# USBHeaders.net
KiCad netlist of a schematic drawn in Altium Designer
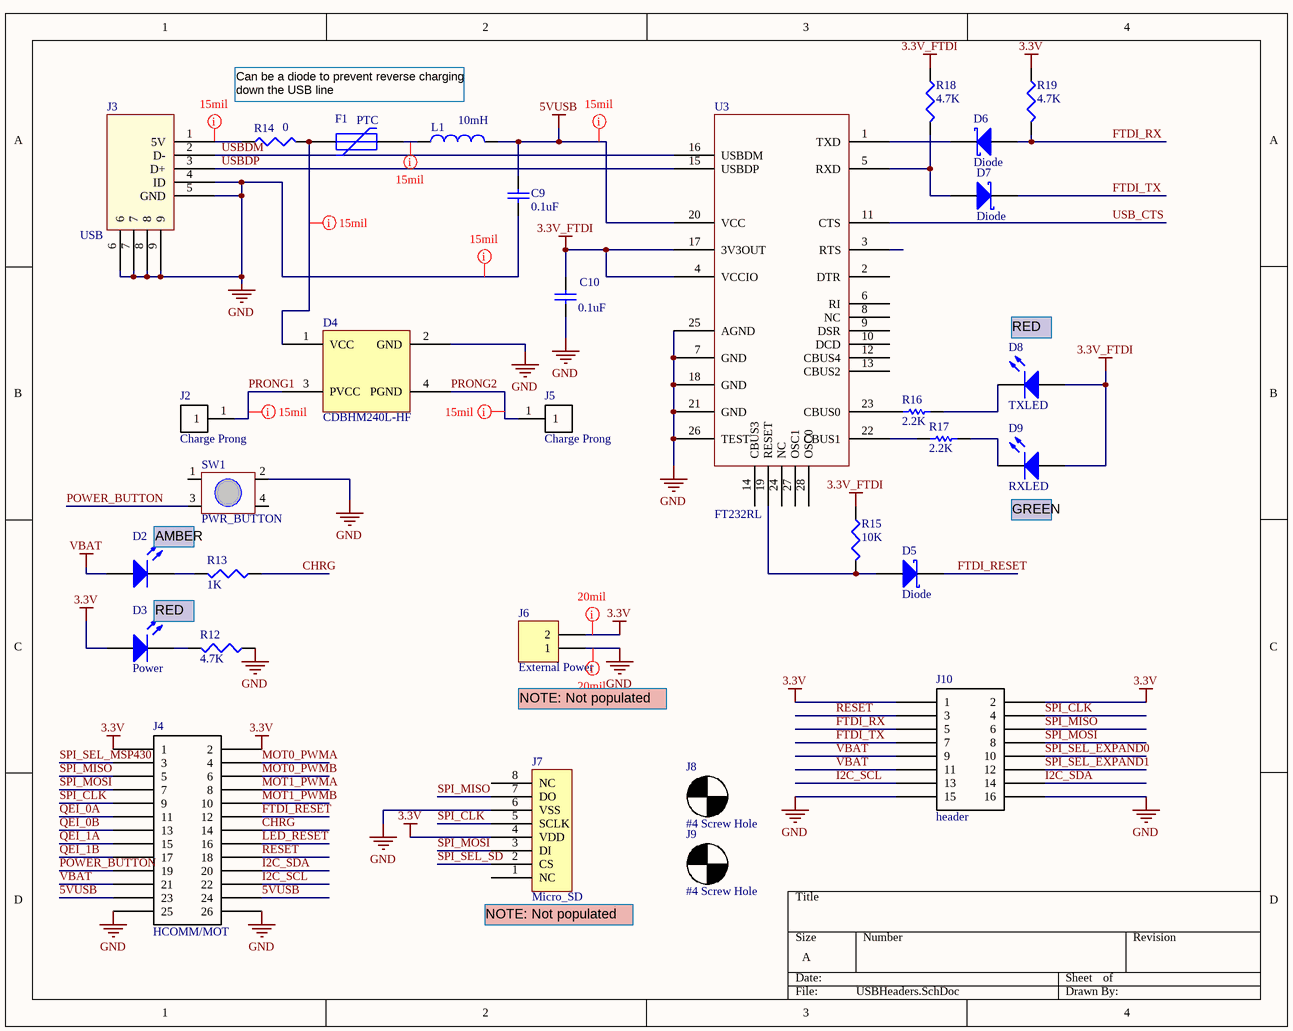
[diagram p0: USBHeaders.SchDoc]

(export (version "E")
  (design (tool "Eeschema 10.0.6"))
  (components
    (comp (ref "C9")
      (value "0.1uF")
      (footprint "CAPC1005L")
      (description "Capacitor")
      (fields (field (name "PUBLISHER") "Altium Limited"))
      (libsource (lib "Miscellaneous Devices") (part "Cap"))
    )
    (comp (ref "C10")
      (value "0.1uF")
      (footprint "CAPC1005L")
      (description "Capacitor")
      (fields (field (name "PUBLISHER") "Altium Limited"))
      (libsource (lib "Miscellaneous Devices") (part "Cap"))
    )
    (comp (ref "D2")
      (value "Charge")
      (footprint "SurfaceMount(603)")
      (description "Typical RED, GREEN, YELLOW, AMBER GaAs LED")
      (fields (field (name "PUBLISHER") "Altium Limited"))
      (libsource (lib "") (part "LED2_1"))
    )
    (comp (ref "D3") (value "Power") (footprint "SurfaceMount(603)") (libsource (lib "mrone") (part "LED")))
    (comp (ref "D4")
      (value "CDBHM240L-HF")
      (footprint "DIODEARRAY_2AMPS")
      (fields (field (name "MPN") "CDBHM240L-HF"))
      (libsource (lib "mrone") (part "DiodeArray2Amps"))
    )
    (comp (ref "D5")
      (value "Diode")
      (footprint "SurfaceMount(603)")
      (libsource (lib "mrone") (part "SchottkeyDiode"))
    )
    (comp (ref "D6")
      (value "Diode")
      (footprint "SurfaceMount(603)")
      (libsource (lib "mrone") (part "SchottkeyDiode"))
    )
    (comp (ref "D7")
      (value "Diode")
      (footprint "SurfaceMount(603)")
      (libsource (lib "mrone") (part "SchottkeyDiode"))
    )
    (comp (ref "D8")
      (value "TXLED")
      (footprint "SurfaceMount(603)")
      (description "Typical RED, GREEN, YELLOW, AMBER GaAs LED")
      (fields (field (name "PUBLISHER") "Altium Limited"))
      (libsource (lib "Miscellaneous Devices") (part "LED2"))
    )
    (comp (ref "D9")
      (value "RXLED")
      (footprint "SurfaceMount(603)")
      (description "Typical RED, GREEN, YELLOW, AMBER GaAs LED")
      (fields (field (name "PUBLISHER") "Altium Limited"))
      (libsource (lib "Miscellaneous Devices") (part "LED2"))
    )
    (comp (ref "F1")
      (value "PTC")
      (footprint "ERJ8G-1206")
      (description "Fuse")
      (fields (field (name "PUBLISHER") "Altium Limited"))
      (libsource (lib "mrone") (part "PTC_FUSE"))
    )
    (comp (ref "J2")
      (value "Charge Prong")
      (footprint "CHARGING_PRONG")
      (description "Charging Prong Hole with Plating")
      (libsource (lib "mrone") (part "CHARGE_PRONG"))
    )
    (comp (ref "J3")
      (value "USB")
      (footprint "USB Minib (thru-hole)")
      (libsource (lib "mrone") (part "USB-ConnTH"))
    )
    (comp (ref "J4")
      (value "HCOMM/MOT")
      (footprint "HeaderSM 13x2")
      (description "Header, 2X20, 50mil, IDC")
      (libsource (lib "mrone") (part "HCOMM/HMOT"))
    )
    (comp (ref "J5")
      (value "Charge Prong")
      (footprint "CHARGING_PRONG")
      (description "Charging Prong Hole with Plating")
      (libsource (lib "mrone") (part "CHARGE_PRONG"))
    )
    (comp (ref "J6")
      (value "External Power")
      (footprint "HDR1X2")
      (description "Header, 2-Pin")
      (fields (field (name "PUBLISHER") "Altium Limited"))
      (libsource (lib "Miscellaneous Connectors") (part "Header 2"))
    )
    (comp (ref "J7") (value "Micro_SD") (footprint "MICRO_SD") (libsource (lib "mrone") (part "MICRO_SD")))
    (comp (ref "J8")
      (value "#4 Screw Hole")
      (footprint "#4_Screw_Hole")
      (description "A mechanical hole for mounting the board")
      (libsource (lib "mrone") (part "Mechanical_Hole"))
    )
    (comp (ref "J9")
      (value "#4 Screw Hole")
      (footprint "#4_Screw_Hole")
      (description "A mechanical hole for mounting the board")
      (libsource (lib "mrone") (part "Mechanical_Hole"))
    )
    (comp (ref "J10")
      (value "header")
      (footprint "HEADERSM 8X2")
      (libsource (lib "mrone") (part "HEADER 8X2"))
    )
    (comp (ref "L1")
      (value "10mH")
      (footprint "INDC2012L")
      (description "Inductor")
      (fields (field (name "PUBLISHER") "Altium Limited"))
      (libsource (lib "Miscellaneous Devices") (part "Inductor"))
    )
    (comp (ref "R12")
      (value "4.7K")
      (footprint "RESC1608L")
      (description "Resistor")
      (fields (field (name "Comment") "Res3") (field (name "PUBLISHER") "Altium Limited"))
      (libsource (lib "Miscellaneous Devices") (part "Res3"))
    )
    (comp (ref "R13")
      (value "1K")
      (footprint "RESC1608L")
      (description "Resistor")
      (fields (field (name "Comment") "Res3") (field (name "PUBLISHER") "Altium Limited"))
      (libsource (lib "Miscellaneous Devices") (part "Res3"))
    )
    (comp (ref "R14")
      (value "0")
      (footprint "RESC1608L")
      (description "Resistor")
      (fields (field (name "Comment") "Res3") (field (name "PUBLISHER") "Altium Limited"))
      (libsource (lib "Miscellaneous Devices") (part "Res3"))
    )
    (comp (ref "R15")
      (value "10K")
      (footprint "RESC1608L")
      (description "Resistor")
      (fields (field (name "Comment") "Res3") (field (name "PUBLISHER") "Altium Limited"))
      (libsource (lib "Miscellaneous Devices") (part "Res3"))
    )
    (comp (ref "R16")
      (value "2.2K")
      (footprint "RESC1608L")
      (description "Resistor")
      (fields (field (name "PUBLISHER") "Altium Limited"))
      (libsource (lib "Miscellaneous Devices") (part "Res1"))
    )
    (comp (ref "R17")
      (value "2.2K")
      (footprint "RESC1608L")
      (description "Resistor")
      (fields (field (name "PUBLISHER") "Altium Limited"))
      (libsource (lib "Miscellaneous Devices") (part "Res1"))
    )
    (comp (ref "R18")
      (value "4.7K")
      (footprint "RESC1608L")
      (description "Resistor")
      (fields (field (name "Comment") "Res3") (field (name "PUBLISHER") "Altium Limited"))
      (libsource (lib "Miscellaneous Devices") (part "Res3"))
    )
    (comp (ref "R19")
      (value "4.7K")
      (footprint "RESC1608L")
      (description "Resistor")
      (fields (field (name "Comment") "Res3") (field (name "PUBLISHER") "Altium Limited"))
      (libsource (lib "Miscellaneous Devices") (part "Res3"))
    )
    (comp (ref "SW1")
      (value "PWR_BUTTON")
      (footprint "SwitchTall-TL330")
      (libsource (lib "mrone") (part "Switch-TL330"))
    )
    (comp (ref "U3") (value "FT232RL") (footprint "SSOP-28") (libsource (lib "mrone") (part "FT232RL")))
  )
  (nets
    (net (code "2") (name "/CHRG") (class "Default")
      (node (ref "J4") (pin "14") (pinfunction "14_14") (pintype "passive"))
      (node (ref "R13") (pin "1") (pinfunction "1_1") (pintype "passive"))
    )
    (net (code "3") (name "/FTDI_RESET") (class "Default")
      (node (ref "D5") (pin "1") (pinfunction "K_1") (pintype "passive"))
      (node (ref "J4") (pin "12") (pinfunction "12_12") (pintype "passive"))
    )
    (net (code "4") (name "/FTDI_RX") (class "Default")
      (node (ref "D6") (pin "2") (pinfunction "A_2") (pintype "passive"))
      (node (ref "J10") (pin "5") (pinfunction "5_5") (pintype "passive"))
      (node (ref "R19") (pin "2") (pinfunction "2_2") (pintype "passive"))
    )
    (net (code "5") (name "/FTDI_TX") (class "Default")
      (node (ref "D7") (pin "1") (pinfunction "K_1") (pintype "passive"))
      (node (ref "J10") (pin "7") (pinfunction "7_7") (pintype "passive"))
    )
    (net (code "6") (name "/I2C_SCL") (class "Default")
      (node (ref "J10") (pin "13") (pinfunction "13_13") (pintype "passive"))
      (node (ref "J4") (pin "22") (pinfunction "22_22") (pintype "passive"))
    )
    (net (code "7") (name "/I2C_SDA") (class "Default")
      (node (ref "J10") (pin "14") (pinfunction "14_14") (pintype "passive"))
      (node (ref "J4") (pin "20") (pinfunction "20_20") (pintype "passive"))
    )
    (net (code "8") (name "/LED_RESET") (class "Default")
      (node (ref "J4") (pin "16") (pinfunction "16_16") (pintype "passive"))
    )
    (net (code "9") (name "/MOT0_PWMA") (class "Default")
      (node (ref "J4") (pin "4") (pinfunction "4_4") (pintype "passive"))
    )
    (net (code "10") (name "/MOT0_PWMB") (class "Default")
      (node (ref "J4") (pin "6") (pinfunction "6_6") (pintype "passive"))
    )
    (net (code "11") (name "/MOT1_PWMA") (class "Default")
      (node (ref "J4") (pin "8") (pinfunction "8_8") (pintype "passive"))
    )
    (net (code "12") (name "/MOT1_PWMB") (class "Default")
      (node (ref "J4") (pin "10") (pinfunction "10_10") (pintype "passive"))
    )
    (net (code "13") (name "/POWER_BUTTON") (class "Default")
      (node (ref "J4") (pin "19") (pinfunction "19_19") (pintype "passive"))
      (node (ref "SW1") (pin "3") (pinfunction "3_3") (pintype "passive"))
    )
    (net (code "14") (name "/PRONG1") (class "Default")
      (node (ref "D4") (pin "3") (pinfunction "PVCC_3") (pintype "passive"))
      (node (ref "J2") (pin "1") (pinfunction "1_1") (pintype "passive"))
    )
    (net (code "15") (name "/PRONG2") (class "Default")
      (node (ref "D4") (pin "4") (pinfunction "PGND_4") (pintype "passive"))
      (node (ref "J5") (pin "1") (pinfunction "1_1") (pintype "passive"))
    )
    (net (code "16") (name "/QEI_0A") (class "Default")
      (node (ref "J4") (pin "11") (pinfunction "11_11") (pintype "passive"))
    )
    (net (code "17") (name "/QEI_0B") (class "Default")
      (node (ref "J4") (pin "13") (pinfunction "13_13") (pintype "passive"))
    )
    (net (code "18") (name "/QEI_1A") (class "Default")
      (node (ref "J4") (pin "15") (pinfunction "15_15") (pintype "passive"))
    )
    (net (code "19") (name "/QEI_1B") (class "Default")
      (node (ref "J4") (pin "17") (pinfunction "17_17") (pintype "passive"))
    )
    (net (code "20") (name "/RESET") (class "Default")
      (node (ref "J10") (pin "3") (pinfunction "3_3") (pintype "passive"))
      (node (ref "J4") (pin "18") (pinfunction "18_18") (pintype "passive"))
    )
    (net (code "21") (name "/SPI_CLK") (class "Default")
      (node (ref "J10") (pin "4") (pinfunction "4_4") (pintype "passive"))
      (node (ref "J4") (pin "9") (pinfunction "9_9") (pintype "passive"))
      (node (ref "J7") (pin "5") (pinfunction "SCLK_5") (pintype "passive"))
    )
    (net (code "22") (name "/SPI_MISO") (class "Default")
      (node (ref "J10") (pin "6") (pinfunction "6_6") (pintype "passive"))
      (node (ref "J4") (pin "5") (pinfunction "5_5") (pintype "passive"))
      (node (ref "J7") (pin "7") (pinfunction "DO_7") (pintype "passive"))
    )
    (net (code "23") (name "/SPI_MOSI") (class "Default")
      (node (ref "J10") (pin "8") (pinfunction "8_8") (pintype "passive"))
      (node (ref "J4") (pin "7") (pinfunction "7_7") (pintype "passive"))
      (node (ref "J7") (pin "3") (pinfunction "DI_3") (pintype "passive"))
    )
    (net (code "24") (name "/SPI_SEL_EXPAND0") (class "Default")
      (node (ref "J10") (pin "10") (pinfunction "10_10") (pintype "passive"))
    )
    (net (code "25") (name "/SPI_SEL_EXPAND1") (class "Default")
      (node (ref "J10") (pin "12") (pinfunction "12_12") (pintype "passive"))
    )
    (net (code "26") (name "/SPI_SEL_MSP430") (class "Default")
      (node (ref "J4") (pin "3") (pinfunction "3_3") (pintype "passive"))
    )
    (net (code "27") (name "/SPI_SEL_SD") (class "Default")
      (node (ref "J7") (pin "2") (pinfunction "CS_2") (pintype "passive"))
    )
    (net (code "28") (name "/USBDM") (class "Default")
      (node (ref "J3") (pin "2") (pinfunction "D-_2") (pintype "passive"))
      (node (ref "U3") (pin "16") (pinfunction "USBDM_16") (pintype "passive"))
    )
    (net (code "29") (name "/USBDP") (class "Default")
      (node (ref "J3") (pin "3") (pinfunction "D+_3") (pintype "passive"))
      (node (ref "U3") (pin "15") (pinfunction "USBDP_15") (pintype "passive"))
    )
    (net (code "30") (name "/USB_CTS") (class "Default")
      (node (ref "U3") (pin "11") (pinfunction "CTS_11") (pintype "passive"))
    )
    (net (code "31") (name "3.3V") (class "Default")
      (node (ref "D3") (pin "1") (pinfunction "A_1") (pintype "passive"))
      (node (ref "J10") (pin "1") (pinfunction "1_1") (pintype "passive"))
      (node (ref "J10") (pin "2") (pinfunction "2_2") (pintype "passive"))
      (node (ref "J4") (pin "1") (pinfunction "1_1") (pintype "passive"))
      (node (ref "J4") (pin "2") (pinfunction "2_2") (pintype "passive"))
      (node (ref "J6") (pin "2") (pinfunction "2_2") (pintype "passive"))
      (node (ref "J7") (pin "4") (pinfunction "VDD_4") (pintype "passive"))
      (node (ref "R19") (pin "1") (pinfunction "1_1") (pintype "passive"))
    )
    (net (code "32") (name "3.3V_FTDI") (class "Default")
      (node (ref "C10") (pin "2") (pinfunction "2_2") (pintype "passive"))
      (node (ref "D8") (pin "1") (pinfunction "A_1") (pintype "passive"))
      (node (ref "D9") (pin "1") (pinfunction "A_1") (pintype "passive"))
      (node (ref "R15") (pin "1") (pinfunction "1_1") (pintype "passive"))
      (node (ref "R18") (pin "1") (pinfunction "1_1") (pintype "passive"))
      (node (ref "U3") (pin "17") (pinfunction "3V3OUT_17") (pintype "passive"))
      (node (ref "U3") (pin "4") (pinfunction "VCCIO_4") (pintype "passive"))
    )
    (net (code "33") (name "5VUSB") (class "Default")
      (node (ref "C9") (pin "2") (pinfunction "2_2") (pintype "passive"))
      (node (ref "J4") (pin "23") (pinfunction "23_23") (pintype "passive"))
      (node (ref "J4") (pin "24") (pinfunction "24_24") (pintype "passive"))
      (node (ref "L1") (pin "2") (pinfunction "2_2") (pintype "passive"))
      (node (ref "U3") (pin "20") (pinfunction "VCC_20") (pintype "passive"))
    )
    (net (code "34") (name "GND") (class "Default")
      (node (ref "C10") (pin "1") (pinfunction "1_1") (pintype "passive"))
      (node (ref "C9") (pin "1") (pinfunction "1_1") (pintype "passive"))
      (node (ref "D4") (pin "2") (pinfunction "GND_2") (pintype "passive"))
      (node (ref "J10") (pin "15") (pinfunction "15_15") (pintype "passive"))
      (node (ref "J10") (pin "16") (pinfunction "16_16") (pintype "passive"))
      (node (ref "J3") (pin "4") (pinfunction "ID_4") (pintype "passive"))
      (node (ref "J3") (pin "5") (pinfunction "GND_5") (pintype "passive"))
      (node (ref "J3") (pin "6") (pinfunction "6_6") (pintype "passive"))
      (node (ref "J3") (pin "7") (pinfunction "7_7") (pintype "passive"))
      (node (ref "J3") (pin "8") (pinfunction "8_8") (pintype "passive"))
      (node (ref "J3") (pin "9") (pinfunction "9_9") (pintype "passive"))
      (node (ref "J4") (pin "25") (pinfunction "25_25") (pintype "passive"))
      (node (ref "J4") (pin "26") (pinfunction "26_26") (pintype "passive"))
      (node (ref "J6") (pin "1") (pinfunction "1_1") (pintype "passive"))
      (node (ref "J7") (pin "6") (pinfunction "VSS_6") (pintype "passive"))
      (node (ref "R12") (pin "1") (pinfunction "1_1") (pintype "passive"))
      (node (ref "SW1") (pin "2") (pinfunction "2_2") (pintype "passive"))
      (node (ref "U3") (pin "18") (pinfunction "GND_18") (pintype "passive"))
      (node (ref "U3") (pin "21") (pinfunction "GND_21") (pintype "passive"))
      (node (ref "U3") (pin "25") (pinfunction "AGND_25") (pintype "passive"))
      (node (ref "U3") (pin "26") (pinfunction "TEST_26") (pintype "passive"))
      (node (ref "U3") (pin "7") (pinfunction "GND_7") (pintype "passive"))
    )
    (net (code "35") (name "Net-(D2-K)") (class "Default")
      (node (ref "D2") (pin "2") (pinfunction "K_2") (pintype "passive"))
      (node (ref "R13") (pin "2") (pinfunction "2_2") (pintype "passive"))
    )
    (net (code "36") (name "Net-(D3-K)") (class "Default")
      (node (ref "D3") (pin "2") (pinfunction "K_2") (pintype "passive"))
      (node (ref "R12") (pin "2") (pinfunction "2_2") (pintype "passive"))
    )
    (net (code "37") (name "Net-(D4-VCC)") (class "Default")
      (node (ref "D4") (pin "1") (pinfunction "VCC_1") (pintype "passive"))
      (node (ref "F1") (pin "2") (pinfunction "2_2") (pintype "passive"))
      (node (ref "R14") (pin "2") (pinfunction "2_2") (pintype "passive"))
    )
    (net (code "38") (name "Net-(D5-A)") (class "Default")
      (node (ref "D5") (pin "2") (pinfunction "A_2") (pintype "passive"))
      (node (ref "R15") (pin "2") (pinfunction "2_2") (pintype "passive"))
      (node (ref "U3") (pin "19") (pinfunction "RESET_19") (pintype "passive"))
    )
    (net (code "39") (name "Net-(D6-K)") (class "Default")
      (node (ref "D6") (pin "1") (pinfunction "K_1") (pintype "passive"))
      (node (ref "U3") (pin "1") (pinfunction "TXD_1") (pintype "passive"))
    )
    (net (code "40") (name "Net-(D7-A)") (class "Default")
      (node (ref "D7") (pin "2") (pinfunction "A_2") (pintype "passive"))
      (node (ref "R18") (pin "2") (pinfunction "2_2") (pintype "passive"))
      (node (ref "U3") (pin "5") (pinfunction "RXD_5") (pintype "passive"))
    )
    (net (code "41") (name "Net-(D8-K)") (class "Default")
      (node (ref "D8") (pin "2") (pinfunction "K_2") (pintype "passive"))
      (node (ref "R16") (pin "2") (pinfunction "2_2") (pintype "passive"))
    )
    (net (code "42") (name "Net-(D9-K)") (class "Default")
      (node (ref "D9") (pin "2") (pinfunction "K_2") (pintype "passive"))
      (node (ref "R17") (pin "2") (pinfunction "2_2") (pintype "passive"))
    )
    (net (code "43") (name "Net-(F1-Pad1)") (class "Default")
      (node (ref "F1") (pin "1") (pinfunction "1_1") (pintype "passive"))
      (node (ref "L1") (pin "1") (pinfunction "1_1") (pintype "passive"))
    )
    (net (code "44") (name "Net-(J3-5V)") (class "Default")
      (node (ref "J3") (pin "1") (pinfunction "5V_1") (pintype "passive"))
      (node (ref "R14") (pin "1") (pinfunction "1_1") (pintype "passive"))
    )
    (net (code "45") (name "Net-(U3-CBUS0)") (class "Default")
      (node (ref "R16") (pin "1") (pinfunction "1_1") (pintype "passive"))
      (node (ref "U3") (pin "23") (pinfunction "CBUS0_23") (pintype "passive"))
    )
    (net (code "46") (name "Net-(U3-CBUS1)") (class "Default")
      (node (ref "R17") (pin "1") (pinfunction "1_1") (pintype "passive"))
      (node (ref "U3") (pin "22") (pinfunction "CBUS1_22") (pintype "passive"))
    )
    (net (code "47") (name "VBAT") (class "Default")
      (node (ref "D2") (pin "1") (pinfunction "A_1") (pintype "passive"))
      (node (ref "J10") (pin "11") (pinfunction "11_11") (pintype "passive"))
      (node (ref "J10") (pin "9") (pinfunction "9_9") (pintype "passive"))
      (node (ref "J4") (pin "21") (pinfunction "21_21") (pintype "passive"))
    )
    (net (code "48") (name "unconnected-(J7-NC-Pad1)") (class "Default")
      (node (ref "J7") (pin "1") (pinfunction "NC_1") (pintype "passive"))
    )
    (net (code "49") (name "unconnected-(J7-NC-Pad8)") (class "Default")
      (node (ref "J7") (pin "8") (pinfunction "NC_8") (pintype "passive"))
    )
    (net (code "50") (name "unconnected-(SW1-Pad1)") (class "Default")
      (node (ref "SW1") (pin "1") (pinfunction "1_1") (pintype "passive"))
    )
    (net (code "51") (name "unconnected-(SW1-Pad4)") (class "Default")
      (node (ref "SW1") (pin "4") (pinfunction "4_4") (pintype "passive"))
    )
    (net (code "52") (name "unconnected-(U3-CBUS2-Pad13)") (class "Default")
      (node (ref "U3") (pin "13") (pinfunction "CBUS2_13") (pintype "passive"))
    )
    (net (code "53") (name "unconnected-(U3-CBUS3-Pad14)") (class "Default")
      (node (ref "U3") (pin "14") (pinfunction "CBUS3_14") (pintype "passive"))
    )
    (net (code "54") (name "unconnected-(U3-CBUS4-Pad12)") (class "Default")
      (node (ref "U3") (pin "12") (pinfunction "CBUS4_12") (pintype "passive"))
    )
    (net (code "55") (name "unconnected-(U3-DCD-Pad10)") (class "Default")
      (node (ref "U3") (pin "10") (pinfunction "DCD_10") (pintype "passive"))
    )
    (net (code "56") (name "unconnected-(U3-DSR-Pad9)") (class "Default")
      (node (ref "U3") (pin "9") (pinfunction "DSR_9") (pintype "passive"))
    )
    (net (code "57") (name "unconnected-(U3-DTR-Pad2)") (class "Default")
      (node (ref "U3") (pin "2") (pinfunction "DTR_2") (pintype "passive"))
    )
    (net (code "58") (name "unconnected-(U3-NC-Pad8)") (class "Default")
      (node (ref "U3") (pin "8") (pinfunction "NC_8") (pintype "passive"))
    )
    (net (code "59") (name "unconnected-(U3-NC-Pad24)") (class "Default")
      (node (ref "U3") (pin "24") (pinfunction "NC_24") (pintype "passive"))
    )
    (net (code "60") (name "unconnected-(U3-OSC0-Pad28)") (class "Default")
      (node (ref "U3") (pin "28") (pinfunction "OSC0_28") (pintype "passive"))
    )
    (net (code "61") (name "unconnected-(U3-OSC1-Pad27)") (class "Default")
      (node (ref "U3") (pin "27") (pinfunction "OSC1_27") (pintype "passive"))
    )
    (net (code "62") (name "unconnected-(U3-RI-Pad6)") (class "Default")
      (node (ref "U3") (pin "6") (pinfunction "RI_6") (pintype "passive"))
    )
    (net (code "63") (name "unconnected-(U3-RTS-Pad3)") (class "Default")
      (node (ref "U3") (pin "3") (pinfunction "RTS_3") (pintype "passive"))
    )
  )
)
